# Power.net
KiCad netlist of a schematic drawn in Altium Designer
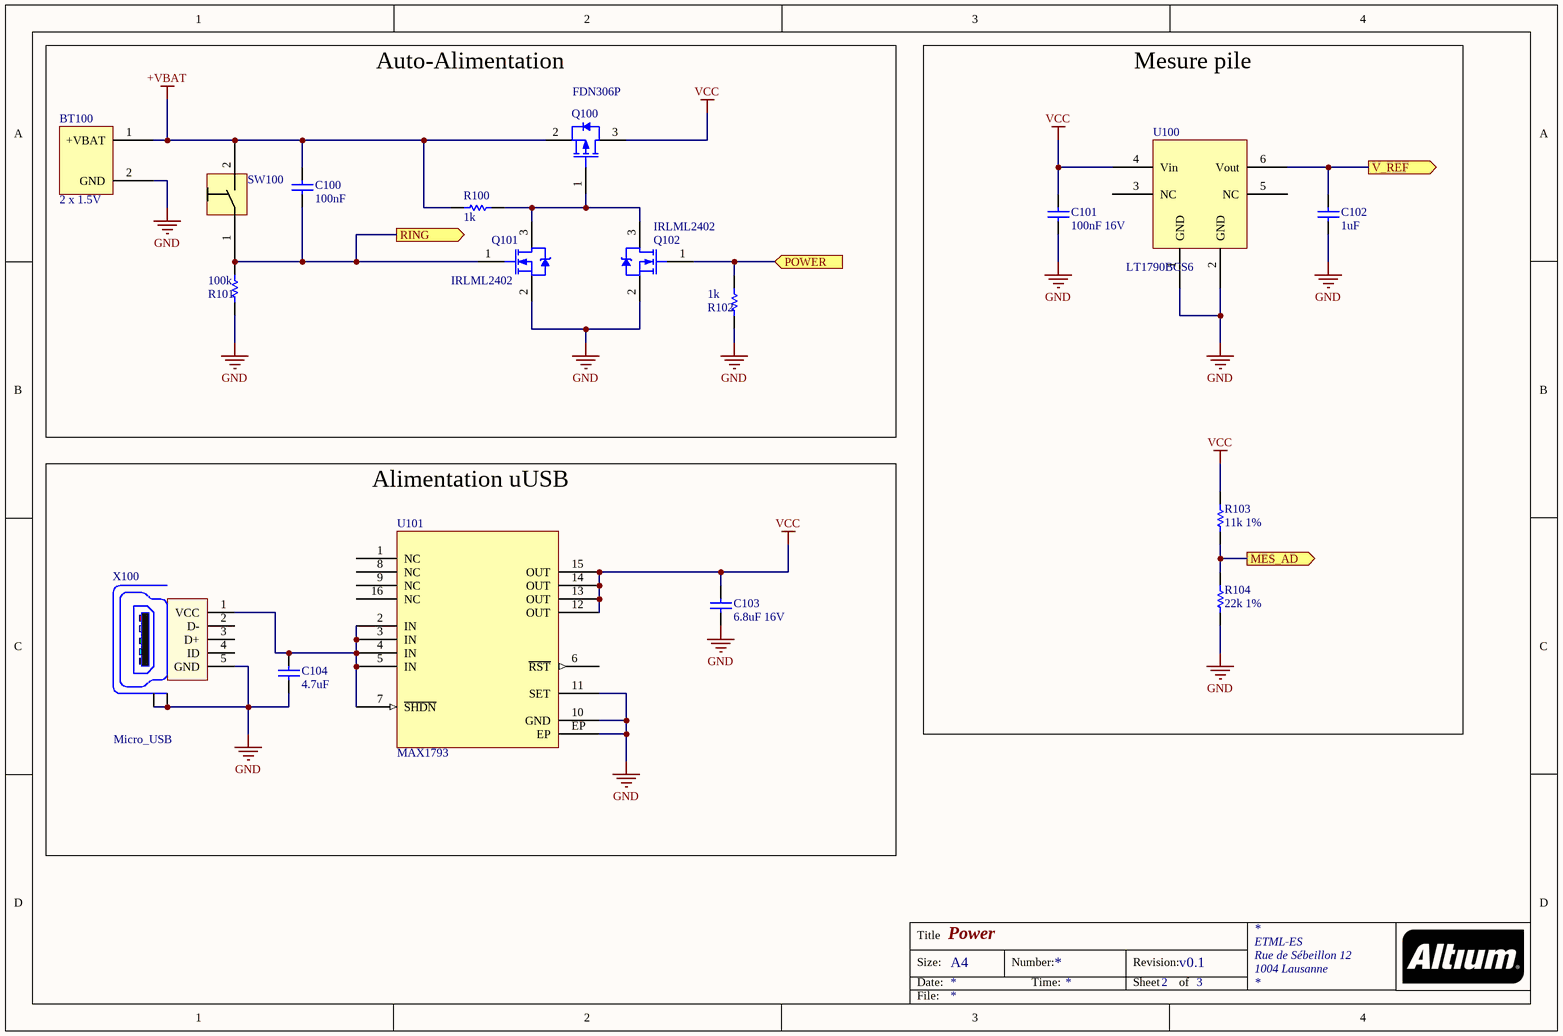
[diagram p0: Power.SchDoc]

(export (version "E")
  (design (tool "Eeschema 10.0.6"))
  (components
    (comp (ref "BT100")
      (value "2 x 1.5V")
      (footprint "BatterySupport")
      (description "Battery Support 2x1.5V type AAA")
      (fields (field (name "MANUFACTURER") "Keystone Electronics") (field (name "PARTNUMBER") "1022"))
      (libsource (lib "CircuitOUT") (part "Battery connector AAA"))
    )
    (comp (ref "C100")
      (value "100nF")
      (footprint "CAPC2013X100X20NL20")
      (description "Chip Capacitor, 100 nF, +/- 10%, 16 V, -55 to 85 degC, 0805 (2012 Metric), RoHS, Tape and Reel")
      (libsource (lib "Altium Content Vault") (part "CMP-1663-00007-1"))
    )
    (comp (ref "C101")
      (value "100nF 16V")
      (footprint "CAPC0805(2012)145_M")
      (description "CAP 100nF 16V ±20% 0805 (2012 Metric) Thickness 1.45mm SMD")
      (libsource (lib "Altium Content Vault") (part "CMP-1036-04404-1"))
    )
    (comp (ref "C102")
      (value "1uF")
      (footprint "CAPC2013X145X50ML20T25")
      (description "Chip Capacitor, 1 uF, 25 V, 10%, -55 to 125 degC, 0805 (2012 Metric), RoHS, Tape and Reel")
      (libsource (lib "Altium Content Vault") (part "CMP-2100-03605-1"))
    )
    (comp (ref "C103")
      (value "6.8uF 16V")
      (footprint "CAPC0805(2012)145_L")
      (description "CAP 6.8uF 16V ±20% 0805 (2012 Metric) Thickness 1.45mm SMD")
      (libsource (lib "Altium Content Vault") (part "CMP-1036-04912-1"))
    )
    (comp (ref "C104")
      (value "4.7uF")
      (footprint "CAPC2013X135X45LL10T25")
      (description "Chip Capacitor, 4.7 uF, +/- 10%, 16 V, -55 to 85 degC, 0805 (2012 Metric), RoHS, Tape and Reel")
      (fields (field (name "PARTNUMBER") "GRM21BR61C475KA88L"))
      (libsource (lib "Altium Content Vault") (part "CMP-1662-00015-2"))
    )
    (comp (ref "Q100")
      (value "FDN306P")
      (footprint "FAIR-SSOT3L-3_V")
      (fields (field (name "MANUFACTURER") "ON Semiconductor"))
      (libsource (lib "Altium Content Vault") (part "CMP-2000-06248-1"))
    )
    (comp (ref "Q101")
      (value "IRLML2402")
      (footprint "INTR-IRLML2402TRPBF-3_V")
      (description "HEXFET(R) Power MOSFET, N-Channel, 20 V, 1.2 A, 3-Pin SOT-23, RoHS, Tape and Reel")
      (fields
        (field (name "MANUFACTURER") "Infineon Technologies")
        (field (name "PARTNUMBER") "IRLML2402TRBF")
      )
      (libsource (lib "Altium Content Vault") (part "CMP-2000-05155-1"))
    )
    (comp (ref "Q102")
      (value "IRLML2402")
      (footprint "INTR-IRLML2402TRPBF-3_V")
      (description "HEXFET(R) Power MOSFET, N-Channel, 20 V, 1.2 A, 3-Pin SOT-23, RoHS, Tape and Reel")
      (fields
        (field (name "MANUFACTURER") "Infineon Technologies")
        (field (name "PARTNUMBER") "IRLML2402TRBF")
      )
      (libsource (lib "Altium Content Vault") (part "CMP-2000-05155-1"))
    )
    (comp (ref "R100")
      (value "1k")
      (footprint "RESC2013X60X35ML10T20")
      (description "Chip Resistor, 1 KOhm, +/- 1%, 125 mW, -55 to 155 degC, 0805 (2012 Metric), RoHS, Tape and Reel")
      (libsource (lib "Altium Content Vault") (part "CMP-2100-03671-1"))
    )
    (comp (ref "R101")
      (value "100k")
      (footprint "RESC2013X60X35ML10T20")
      (description "Chip Resistor, 100 KOhm, +/- 1%, 125 mW, -55 to 155 degC, 0805 (2012 Metric), RoHS, Tape and Reel")
      (libsource (lib "Altium Content Vault") (part "CMP-2100-03671-1"))
    )
    (comp (ref "R102")
      (value "1k")
      (footprint "RESC2013X60X35ML10T20")
      (description "Chip Resistor, 1 KOhm, +/- 1%, 125 mW, -55 to 155 degC, 0805 (2012 Metric), RoHS, Tape and Reel")
      (libsource (lib "Altium Content Vault") (part "CMP-2100-03671-1"))
    )
    (comp (ref "R103")
      (value "11k 1%")
      (footprint "RESC0805(2012)_N")
      (description "11k 0.125W 0805 (2012 Metric)  SMD")
      (libsource (lib "Altium Content Vault") (part "CMP-1013-00075-1"))
    )
    (comp (ref "R104")
      (value "22k 1%")
      (footprint "RESC0805(2012)_L")
      (description "22k 0.125W  0805 (2012 Metric)  SMD")
      (libsource (lib "Altium Content Vault") (part "CMP-1013-00082-1"))
    )
    (comp (ref "SW100")
      (value "Poussoir")
      (footprint "Switch_Schurter")
      (description "Switch 12.7x12.7x17.5")
      (fields (field (name "MANUFACTURER") "Schurter"))
      (libsource (lib "CircuitOUT") (part "Switch_Schurter"))
    )
    (comp (ref "U100")
      (value "LT1790BCS6")
      (footprint "SOT-23")
      (description "IC VREF SERIES 2.048V SOT23-6")
      (fields
        (field (name "MANUFACTURER") "Linear Technology")
        (field (name "PARTNUMBER") "LT1790BCS6-2.048#TRMPBF")
      )
      (libsource (lib "CircuitOUT") (part "LT1790"))
    )
    (comp (ref "U101")
      (value "MAX1793")
      (footprint "TSOP65P640X110_HS-17N")
      (description "IC REG LINEAR POS ADJ 1A 16TSSOP")
      (fields (field (name "MANUFACTURER") "Maxim Integrated"))
      (libsource (lib "CircuitOUT") (part "MAX1793"))
    )
    (comp (ref "X100")
      (value "Micro_USB")
      (footprint "Micro_USB")
      (description "WR-COM_USB_Micro Type B_Horizontal_SMT")
      (fields
        (field (name "MANUFACTURER") "Würth Elektronik eiSos GmbH")
        (field (name "PARTNUMBER") "629105150521")
      )
      (libsource (lib "CircuitOUT") (part "WR-Communication Connectors 629105150521"))
    )
  )
  (nets
    (net (code "1") (name "+VBAT") (class "Default")
      (node (ref "BT100") (pin "1") (pinfunction "+VBAT_1") (pintype "power_in"))
      (node (ref "C100") (pin "2") (pinfunction "2_2") (pintype "passive"))
      (node (ref "Q100") (pin "2") (pinfunction "SOURCE_2") (pintype "passive"))
      (node (ref "R100") (pin "2") (pinfunction "2_2") (pintype "passive"))
      (node (ref "SW100") (pin "2") (pinfunction "2_2") (pintype "passive"))
    )
    (net (code "2") (name "/MES_AD") (class "Default")
      (node (ref "R103") (pin "1") (pinfunction "1_1") (pintype "passive"))
      (node (ref "R104") (pin "2") (pinfunction "2_2") (pintype "passive"))
    )
    (net (code "3") (name "/POWER") (class "Default")
      (node (ref "Q102") (pin "1") (pinfunction "G_1") (pintype "passive"))
      (node (ref "R102") (pin "2") (pinfunction "2_2") (pintype "passive"))
    )
    (net (code "4") (name "/RING") (class "Default")
      (node (ref "C100") (pin "1") (pinfunction "1_1") (pintype "passive"))
      (node (ref "Q101") (pin "1") (pinfunction "G_1") (pintype "passive"))
      (node (ref "R101") (pin "2") (pinfunction "2_2") (pintype "passive"))
      (node (ref "SW100") (pin "1") (pinfunction "1_1") (pintype "passive"))
    )
    (net (code "5") (name "/V_REF") (class "Default")
      (node (ref "C102") (pin "2") (pinfunction "2_2") (pintype "passive"))
      (node (ref "U100") (pin "6") (pinfunction "Vout_6") (pintype "passive"))
    )
    (net (code "6") (name "GND") (class "Default")
      (node (ref "BT100") (pin "2") (pinfunction "GND_2") (pintype "power_in"))
      (node (ref "C101") (pin "1") (pinfunction "1_1") (pintype "passive"))
      (node (ref "C102") (pin "1") (pinfunction "1_1") (pintype "passive"))
      (node (ref "C103") (pin "1") (pinfunction "1_1") (pintype "passive"))
      (node (ref "C104") (pin "1") (pinfunction "1_1") (pintype "passive"))
      (node (ref "Q101") (pin "2") (pinfunction "S_2") (pintype "passive"))
      (node (ref "Q102") (pin "2") (pinfunction "S_2") (pintype "passive"))
      (node (ref "R101") (pin "1") (pinfunction "1_1") (pintype "passive"))
      (node (ref "R102") (pin "1") (pinfunction "1_1") (pintype "passive"))
      (node (ref "R104") (pin "1") (pinfunction "1_1") (pintype "passive"))
      (node (ref "U100") (pin "1") (pinfunction "GND_1") (pintype "passive"))
      (node (ref "U100") (pin "2") (pinfunction "GND_2") (pintype "passive"))
      (node (ref "U101") (pin "10") (pinfunction "GND_10") (pintype "passive"))
      (node (ref "U101") (pin "11") (pinfunction "SET_11") (pintype "passive"))
      (node (ref "U101") (pin "EP") (pinfunction "EP_EP") (pintype "passive"))
      (node (ref "X100") (pin "5") (pinfunction "GND_5") (pintype "passive"))
      (node (ref "X100") (pin "Z1") (pinfunction "Shield_Z1") (pintype "passive"))
      (node (ref "X100") (pin "Z2") (pinfunction "Shield_Z2") (pintype "passive"))
    )
    (net (code "7") (name "Net-(Q100-GATE)") (class "Default")
      (node (ref "Q100") (pin "1") (pinfunction "GATE_1") (pintype "passive"))
      (node (ref "Q101") (pin "3") (pinfunction "D_3") (pintype "passive"))
      (node (ref "Q102") (pin "3") (pinfunction "D_3") (pintype "passive"))
      (node (ref "R100") (pin "1") (pinfunction "1_1") (pintype "passive"))
    )
    (net (code "8") (name "Net-(U101-~{SHDN})") (class "Default")
      (node (ref "C104") (pin "2") (pinfunction "2_2") (pintype "passive"))
      (node (ref "U101") (pin "2") (pinfunction "IN_2") (pintype "passive"))
      (node (ref "U101") (pin "3") (pinfunction "IN_3") (pintype "passive"))
      (node (ref "U101") (pin "4") (pinfunction "IN_4") (pintype "passive"))
      (node (ref "U101") (pin "5") (pinfunction "IN_5") (pintype "passive"))
      (node (ref "U101") (pin "7") (pinfunction "~{SHDN}_7") (pintype "input"))
      (node (ref "X100") (pin "1") (pinfunction "VCC_1") (pintype "passive"))
    )
    (net (code "9") (name "VCC") (class "Default")
      (node (ref "C101") (pin "2") (pinfunction "2_2") (pintype "passive"))
      (node (ref "C103") (pin "2") (pinfunction "2_2") (pintype "passive"))
      (node (ref "Q100") (pin "3") (pinfunction "DRAIN_3") (pintype "passive"))
      (node (ref "R103") (pin "2") (pinfunction "2_2") (pintype "passive"))
      (node (ref "U100") (pin "4") (pinfunction "Vin_4") (pintype "passive"))
      (node (ref "U101") (pin "12") (pinfunction "OUT_12") (pintype "passive"))
      (node (ref "U101") (pin "13") (pinfunction "OUT_13") (pintype "passive"))
      (node (ref "U101") (pin "14") (pinfunction "OUT_14") (pintype "passive"))
      (node (ref "U101") (pin "15") (pinfunction "OUT_15") (pintype "passive"))
    )
    (net (code "10") (name "unconnected-(U100-NC-Pad3)") (class "Default")
      (node (ref "U100") (pin "3") (pinfunction "NC_3") (pintype "passive"))
    )
    (net (code "11") (name "unconnected-(U100-NC-Pad5)") (class "Default")
      (node (ref "U100") (pin "5") (pinfunction "NC_5") (pintype "passive"))
    )
    (net (code "12") (name "unconnected-(U101-NC-Pad1)") (class "Default")
      (node (ref "U101") (pin "1") (pinfunction "NC_1") (pintype "passive"))
    )
    (net (code "13") (name "unconnected-(U101-NC-Pad8)") (class "Default")
      (node (ref "U101") (pin "8") (pinfunction "NC_8") (pintype "passive"))
    )
    (net (code "14") (name "unconnected-(U101-NC-Pad9)") (class "Default")
      (node (ref "U101") (pin "9") (pinfunction "NC_9") (pintype "passive"))
    )
    (net (code "15") (name "unconnected-(U101-NC-Pad16)") (class "Default")
      (node (ref "U101") (pin "16") (pinfunction "NC_16") (pintype "passive"))
    )
    (net (code "16") (name "unconnected-(U101-~{RST}-Pad6)") (class "Default")
      (node (ref "U101") (pin "6") (pinfunction "~{RST}_6") (pintype "output"))
    )
    (net (code "17") (name "unconnected-(X100-D+-Pad3)") (class "Default")
      (node (ref "X100") (pin "3") (pinfunction "D+_3") (pintype "passive"))
    )
    (net (code "18") (name "unconnected-(X100-D--Pad2)") (class "Default")
      (node (ref "X100") (pin "2") (pinfunction "D-_2") (pintype "passive"))
    )
    (net (code "19") (name "unconnected-(X100-ID-Pad4)") (class "Default")
      (node (ref "X100") (pin "4") (pinfunction "ID_4") (pintype "passive"))
    )
  )
)
